# design.net
KiCad netlist of a schematic drawn in Altium Designer
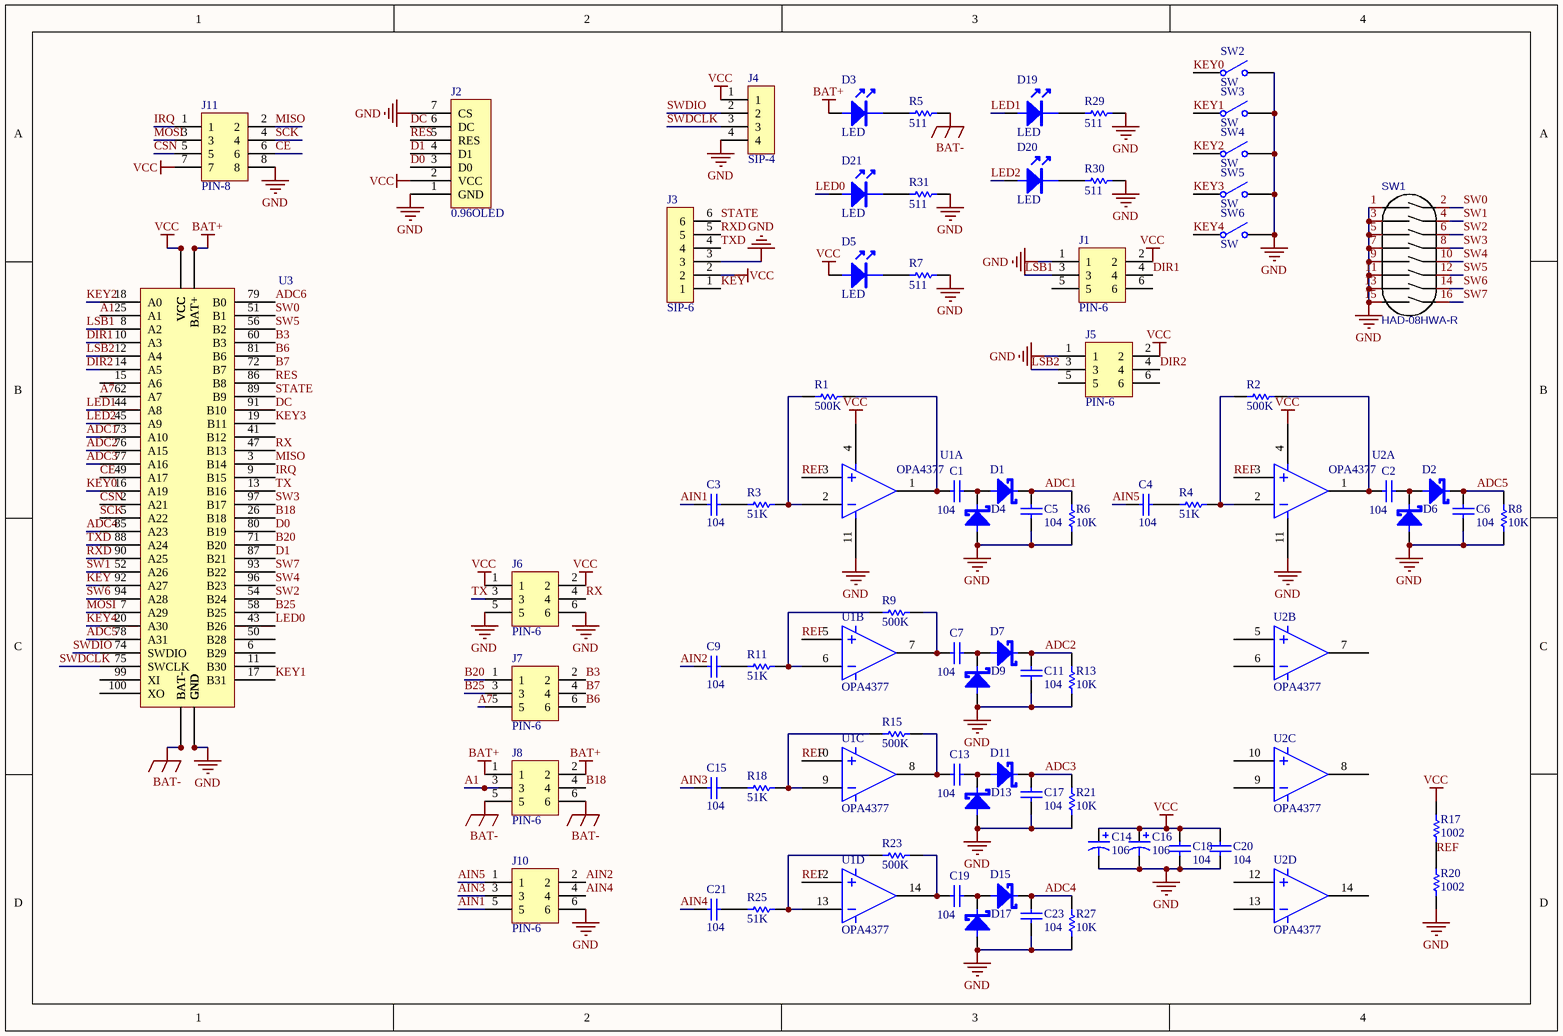
[diagram p0: 原理图.SchDoc]

(export (version "E")
  (design (tool "Eeschema 10.0.6"))
  (components
    (comp (ref "C1")
      (value "104")
      (footprint "C0603")
      (description "Capacitor")
      (fields (field (name "PUBLISHER") "Altium Limited"))
      (libsource (lib "容阻感") (part "电容"))
    )
    (comp (ref "C2")
      (value "104")
      (footprint "C0603")
      (description "Capacitor")
      (fields (field (name "PUBLISHER") "Altium Limited"))
      (libsource (lib "容阻感") (part "电容"))
    )
    (comp (ref "C3")
      (value "104")
      (footprint "C0603")
      (description "Capacitor")
      (fields (field (name "PUBLISHER") "Altium Limited"))
      (libsource (lib "容阻感") (part "电容"))
    )
    (comp (ref "C4")
      (value "104")
      (footprint "C0603")
      (description "Capacitor")
      (fields (field (name "PUBLISHER") "Altium Limited"))
      (libsource (lib "容阻感") (part "电容"))
    )
    (comp (ref "C5")
      (value "104")
      (footprint "C0603")
      (description "Capacitor")
      (fields (field (name "PUBLISHER") "Altium Limited"))
      (libsource (lib "容阻感") (part "电容"))
    )
    (comp (ref "C6")
      (value "104")
      (footprint "C0603")
      (description "Capacitor")
      (fields (field (name "PUBLISHER") "Altium Limited"))
      (libsource (lib "容阻感") (part "电容"))
    )
    (comp (ref "C7")
      (value "104")
      (footprint "C0603")
      (description "Capacitor")
      (fields (field (name "PUBLISHER") "Altium Limited"))
      (libsource (lib "容阻感") (part "电容"))
    )
    (comp (ref "C9")
      (value "104")
      (footprint "C0603")
      (description "Capacitor")
      (fields (field (name "PUBLISHER") "Altium Limited"))
      (libsource (lib "容阻感") (part "电容"))
    )
    (comp (ref "C11")
      (value "104")
      (footprint "C0603")
      (description "Capacitor")
      (fields (field (name "PUBLISHER") "Altium Limited"))
      (libsource (lib "容阻感") (part "电容"))
    )
    (comp (ref "C13")
      (value "104")
      (footprint "C0603")
      (description "Capacitor")
      (fields (field (name "PUBLISHER") "Altium Limited"))
      (libsource (lib "容阻感") (part "电容"))
    )
    (comp (ref "C14")
      (value "106")
      (footprint "3216-ce")
      (description "Polarized Capacitor (Axial)")
      (fields (field (name "PUBLISHER") "Altium Limited"))
      (libsource (lib "容阻感") (part "电解电容"))
    )
    (comp (ref "C15")
      (value "104")
      (footprint "C0603")
      (description "Capacitor")
      (fields (field (name "PUBLISHER") "Altium Limited"))
      (libsource (lib "容阻感") (part "电容"))
    )
    (comp (ref "C16")
      (value "106")
      (footprint "3216-ce")
      (description "Polarized Capacitor (Axial)")
      (fields (field (name "PUBLISHER") "Altium Limited"))
      (libsource (lib "容阻感") (part "电解电容"))
    )
    (comp (ref "C17")
      (value "104")
      (footprint "C0603")
      (description "Capacitor")
      (fields (field (name "PUBLISHER") "Altium Limited"))
      (libsource (lib "容阻感") (part "电容"))
    )
    (comp (ref "C18")
      (value "104")
      (footprint "C0603")
      (description "Capacitor")
      (fields (field (name "PUBLISHER") "Altium Limited"))
      (libsource (lib "容阻感") (part "电容"))
    )
    (comp (ref "C19")
      (value "104")
      (footprint "C0603")
      (description "Capacitor")
      (fields (field (name "PUBLISHER") "Altium Limited"))
      (libsource (lib "容阻感") (part "电容"))
    )
    (comp (ref "C20")
      (value "104")
      (footprint "C0603")
      (description "Capacitor")
      (fields (field (name "PUBLISHER") "Altium Limited"))
      (libsource (lib "容阻感") (part "电容"))
    )
    (comp (ref "C21")
      (value "104")
      (footprint "C0603")
      (description "Capacitor")
      (fields (field (name "PUBLISHER") "Altium Limited"))
      (libsource (lib "容阻感") (part "电容"))
    )
    (comp (ref "C23")
      (value "104")
      (footprint "C0603")
      (description "Capacitor")
      (fields (field (name "PUBLISHER") "Altium Limited"))
      (libsource (lib "容阻感") (part "电容"))
    )
    (comp (ref "D1")
      (value "肖特基")
      (footprint "SOD-523")
      (description "Schottky Diode")
      (libsource (lib "管子、") (part "肖特基"))
    )
    (comp (ref "D2")
      (value "肖特基")
      (footprint "SOD-523")
      (description "Schottky Diode")
      (libsource (lib "管子、") (part "肖特基"))
    )
    (comp (ref "D3") (value "LED") (footprint "LED 0603G") (libsource (lib "管子、") (part "LED")))
    (comp (ref "D4")
      (value "肖特基")
      (footprint "SOD-523")
      (description "Schottky Diode")
      (libsource (lib "管子、") (part "肖特基"))
    )
    (comp (ref "D5") (value "LED") (footprint "LED 0603G") (libsource (lib "管子、") (part "LED")))
    (comp (ref "D6")
      (value "肖特基")
      (footprint "SOD-523")
      (description "Schottky Diode")
      (libsource (lib "管子、") (part "肖特基"))
    )
    (comp (ref "D7")
      (value "肖特基")
      (footprint "SOD-523")
      (description "Schottky Diode")
      (libsource (lib "管子、") (part "肖特基"))
    )
    (comp (ref "D9")
      (value "肖特基")
      (footprint "SOD-523")
      (description "Schottky Diode")
      (libsource (lib "管子、") (part "肖特基"))
    )
    (comp (ref "D11")
      (value "肖特基")
      (footprint "SOD-523")
      (description "Schottky Diode")
      (libsource (lib "管子、") (part "肖特基"))
    )
    (comp (ref "D13")
      (value "肖特基")
      (footprint "SOD-523")
      (description "Schottky Diode")
      (libsource (lib "管子、") (part "肖特基"))
    )
    (comp (ref "D15")
      (value "肖特基")
      (footprint "SOD-523")
      (description "Schottky Diode")
      (libsource (lib "管子、") (part "肖特基"))
    )
    (comp (ref "D17")
      (value "肖特基")
      (footprint "SOD-523")
      (description "Schottky Diode")
      (libsource (lib "管子、") (part "肖特基"))
    )
    (comp (ref "D19") (value "LED") (footprint "LED 0603G") (libsource (lib "管子、") (part "LED")))
    (comp (ref "D20") (value "LED") (footprint "LED 0603G") (libsource (lib "管子、") (part "LED")))
    (comp (ref "D21") (value "LED") (footprint "LED 0603G") (libsource (lib "管子、") (part "LED")))
    (comp (ref "J1") (value "PIN-6") (footprint "2.54简易牛角座6P") (libsource (lib "接插件") (part "PIN-6")))
    (comp (ref "J2") (value "0.96OLED") (footprint "OLED 0.96") (libsource (lib "接插件") (part "OLED_SPI")))
    (comp (ref "J3") (value "SIP-6") (footprint "2.54排针1X6") (libsource (lib "接插件") (part "SIP-6")))
    (comp (ref "J4") (value "SIP-4") (footprint "XH2.54-4AB") (libsource (lib "接插件") (part "SIP-4")))
    (comp (ref "J5") (value "PIN-6") (footprint "2.54简易牛角座6P") (libsource (lib "接插件") (part "PIN-6")))
    (comp (ref "J6") (value "PIN-6") (footprint "P6smd") (libsource (lib "接插件") (part "PIN-6")))
    (comp (ref "J7") (value "PIN-6") (footprint "P6smd") (libsource (lib "接插件") (part "PIN-6")))
    (comp (ref "J8") (value "PIN-6") (footprint "P6smd") (libsource (lib "接插件") (part "PIN-6")))
    (comp (ref "J10") (value "PIN-6") (footprint "P6smd") (libsource (lib "接插件") (part "PIN-6")))
    (comp (ref "J11") (value "PIN-8") (footprint "2.54排针2X4") (libsource (lib "接插件") (part "PIN-8")))
    (comp (ref "R1")
      (value "500K")
      (footprint "R0603")
      (description "Resistor")
      (fields (field (name "PUBLISHER") "Altium Limited"))
      (libsource (lib "容阻感") (part "电阻"))
    )
    (comp (ref "R2")
      (value "500K")
      (footprint "R0603")
      (description "Resistor")
      (fields (field (name "PUBLISHER") "Altium Limited"))
      (libsource (lib "容阻感") (part "电阻"))
    )
    (comp (ref "R3")
      (value "51K")
      (footprint "R0603")
      (description "Resistor")
      (fields (field (name "PUBLISHER") "Altium Limited"))
      (libsource (lib "容阻感") (part "电阻"))
    )
    (comp (ref "R4")
      (value "51K")
      (footprint "R0603")
      (description "Resistor")
      (fields (field (name "PUBLISHER") "Altium Limited"))
      (libsource (lib "容阻感") (part "电阻"))
    )
    (comp (ref "R5")
      (value "511")
      (footprint "R0603")
      (description "Resistor")
      (fields (field (name "PUBLISHER") "Altium Limited"))
      (libsource (lib "容阻感") (part "电阻"))
    )
    (comp (ref "R6")
      (value "10K")
      (footprint "R0603")
      (description "Resistor")
      (fields (field (name "PUBLISHER") "Altium Limited"))
      (libsource (lib "容阻感") (part "电阻"))
    )
    (comp (ref "R7")
      (value "511")
      (footprint "R0603")
      (description "Resistor")
      (fields (field (name "PUBLISHER") "Altium Limited"))
      (libsource (lib "容阻感") (part "电阻"))
    )
    (comp (ref "R8")
      (value "10K")
      (footprint "R0603")
      (description "Resistor")
      (fields (field (name "PUBLISHER") "Altium Limited"))
      (libsource (lib "容阻感") (part "电阻"))
    )
    (comp (ref "R9")
      (value "500K")
      (footprint "R0603")
      (description "Resistor")
      (fields (field (name "PUBLISHER") "Altium Limited"))
      (libsource (lib "容阻感") (part "电阻"))
    )
    (comp (ref "R11")
      (value "51K")
      (footprint "R0603")
      (description "Resistor")
      (fields (field (name "PUBLISHER") "Altium Limited"))
      (libsource (lib "容阻感") (part "电阻"))
    )
    (comp (ref "R13")
      (value "10K")
      (footprint "R0603")
      (description "Resistor")
      (fields (field (name "PUBLISHER") "Altium Limited"))
      (libsource (lib "容阻感") (part "电阻"))
    )
    (comp (ref "R15")
      (value "500K")
      (footprint "R0603")
      (description "Resistor")
      (fields (field (name "PUBLISHER") "Altium Limited"))
      (libsource (lib "容阻感") (part "电阻"))
    )
    (comp (ref "R17")
      (value "1002")
      (footprint "R0603")
      (description "Resistor")
      (fields (field (name "PUBLISHER") "Altium Limited"))
      (libsource (lib "容阻感") (part "电阻"))
    )
    (comp (ref "R18")
      (value "51K")
      (footprint "R0603")
      (description "Resistor")
      (fields (field (name "PUBLISHER") "Altium Limited"))
      (libsource (lib "容阻感") (part "电阻"))
    )
    (comp (ref "R20")
      (value "1002")
      (footprint "R0603")
      (description "Resistor")
      (fields (field (name "PUBLISHER") "Altium Limited"))
      (libsource (lib "容阻感") (part "电阻"))
    )
    (comp (ref "R21")
      (value "10K")
      (footprint "R0603")
      (description "Resistor")
      (fields (field (name "PUBLISHER") "Altium Limited"))
      (libsource (lib "容阻感") (part "电阻"))
    )
    (comp (ref "R23")
      (value "500K")
      (footprint "R0603")
      (description "Resistor")
      (fields (field (name "PUBLISHER") "Altium Limited"))
      (libsource (lib "容阻感") (part "电阻"))
    )
    (comp (ref "R25")
      (value "51K")
      (footprint "R0603")
      (description "Resistor")
      (fields (field (name "PUBLISHER") "Altium Limited"))
      (libsource (lib "容阻感") (part "电阻"))
    )
    (comp (ref "R27")
      (value "10K")
      (footprint "R0603")
      (description "Resistor")
      (fields (field (name "PUBLISHER") "Altium Limited"))
      (libsource (lib "容阻感") (part "电阻"))
    )
    (comp (ref "R29")
      (value "511")
      (footprint "R0603")
      (description "Resistor")
      (fields (field (name "PUBLISHER") "Altium Limited"))
      (libsource (lib "容阻感") (part "电阻"))
    )
    (comp (ref "R30")
      (value "511")
      (footprint "R0603")
      (description "Resistor")
      (fields (field (name "PUBLISHER") "Altium Limited"))
      (libsource (lib "容阻感") (part "电阻"))
    )
    (comp (ref "R31")
      (value "511")
      (footprint "R0603")
      (description "Resistor")
      (fields (field (name "PUBLISHER") "Altium Limited"))
      (libsource (lib "容阻感") (part "电阻"))
    )
    (comp (ref "SW1")
      (value "HAD-08HWA-R")
      (footprint "拨码MCEMR-08-T")
      (fields (field (name "BOM_SUPPLIER PART") "C4682"))
      (libsource (lib "接插件") (part "8位拨码"))
    )
    (comp (ref "SW2")
      (value "SW")
      (footprint "SWT6*3")
      (description "Single-Pole, Single-Throw Switch")
      (libsource (lib "接插件") (part "Switch"))
    )
    (comp (ref "SW3")
      (value "SW")
      (footprint "SWT6*3")
      (description "Single-Pole, Single-Throw Switch")
      (libsource (lib "接插件") (part "Switch"))
    )
    (comp (ref "SW4")
      (value "SW")
      (footprint "SWT6*3")
      (description "Single-Pole, Single-Throw Switch")
      (libsource (lib "接插件") (part "Switch"))
    )
    (comp (ref "SW5")
      (value "SW")
      (footprint "SWT6*3")
      (description "Single-Pole, Single-Throw Switch")
      (libsource (lib "接插件") (part "Switch"))
    )
    (comp (ref "SW6")
      (value "SW")
      (footprint "SWT6*3")
      (description "Single-Pole, Single-Throw Switch")
      (libsource (lib "接插件") (part "Switch"))
    )
    (comp (ref "U1") (value "OPA4377") (footprint "TSSOP-14") (libsource (lib "IC") (part "4运放")))
    (comp (ref "U2") (value "OPA4377") (footprint "TSSOP-14") (libsource (lib "IC") (part "4运放")))
    (comp (ref "U3") (value "主控&驱动") (footprint "核心") (libsource (lib "接插件") (part "核心")))
  )
  (nets
    (net (code "1") (name "/A1") (class "Default")
      (node (ref "J8") (pin "3") (pinfunction "3_3") (pintype "passive"))
      (node (ref "U3") (pin "25") (pinfunction "A1_25") (pintype "passive"))
    )
    (net (code "2") (name "/A7") (class "Default")
      (node (ref "J7") (pin "5") (pinfunction "5_5") (pintype "passive"))
      (node (ref "U3") (pin "62") (pinfunction "A7_62") (pintype "passive"))
    )
    (net (code "3") (name "/ADC1") (class "Default")
      (node (ref "C5") (pin "2") (pinfunction "2_2") (pintype "passive"))
      (node (ref "D1") (pin "2") (pinfunction "K_2") (pintype "passive"))
      (node (ref "R6") (pin "1") (pinfunction "1_1") (pintype "passive"))
      (node (ref "U3") (pin "73") (pinfunction "A10_73") (pintype "passive"))
    )
    (net (code "4") (name "/ADC2") (class "Default")
      (node (ref "C11") (pin "2") (pinfunction "2_2") (pintype "passive"))
      (node (ref "D7") (pin "2") (pinfunction "K_2") (pintype "passive"))
      (node (ref "R13") (pin "1") (pinfunction "1_1") (pintype "passive"))
      (node (ref "U3") (pin "76") (pinfunction "A15_76") (pintype "passive"))
    )
    (net (code "5") (name "/ADC3") (class "Default")
      (node (ref "C17") (pin "2") (pinfunction "2_2") (pintype "passive"))
      (node (ref "D11") (pin "2") (pinfunction "K_2") (pintype "passive"))
      (node (ref "R21") (pin "1") (pinfunction "1_1") (pintype "passive"))
      (node (ref "U3") (pin "77") (pinfunction "A16_77") (pintype "passive"))
    )
    (net (code "6") (name "/ADC4") (class "Default")
      (node (ref "C23") (pin "2") (pinfunction "2_2") (pintype "passive"))
      (node (ref "D15") (pin "2") (pinfunction "K_2") (pintype "passive"))
      (node (ref "R27") (pin "1") (pinfunction "1_1") (pintype "passive"))
      (node (ref "U3") (pin "85") (pinfunction "A23_85") (pintype "passive"))
    )
    (net (code "7") (name "/ADC5") (class "Default")
      (node (ref "C6") (pin "2") (pinfunction "2_2") (pintype "passive"))
      (node (ref "D2") (pin "2") (pinfunction "K_2") (pintype "passive"))
      (node (ref "R8") (pin "1") (pinfunction "1_1") (pintype "passive"))
      (node (ref "U3") (pin "78") (pinfunction "A31_78") (pintype "passive"))
    )
    (net (code "8") (name "/ADC6") (class "Default")
      (node (ref "U3") (pin "79") (pinfunction "B0_79") (pintype "passive"))
    )
    (net (code "9") (name "/AIN1") (class "Default")
      (node (ref "C3") (pin "1") (pinfunction "1_1") (pintype "passive"))
      (node (ref "J10") (pin "5") (pinfunction "5_5") (pintype "passive"))
    )
    (net (code "10") (name "/AIN2") (class "Default")
      (node (ref "C9") (pin "1") (pinfunction "1_1") (pintype "passive"))
      (node (ref "J10") (pin "2") (pinfunction "2_2") (pintype "passive"))
    )
    (net (code "11") (name "/AIN3") (class "Default")
      (node (ref "C15") (pin "1") (pinfunction "1_1") (pintype "passive"))
      (node (ref "J10") (pin "3") (pinfunction "3_3") (pintype "passive"))
    )
    (net (code "12") (name "/AIN4") (class "Default")
      (node (ref "C21") (pin "1") (pinfunction "1_1") (pintype "passive"))
      (node (ref "J10") (pin "4") (pinfunction "4_4") (pintype "passive"))
    )
    (net (code "13") (name "/AIN5") (class "Default")
      (node (ref "C4") (pin "1") (pinfunction "1_1") (pintype "passive"))
      (node (ref "J10") (pin "1") (pinfunction "1_1") (pintype "passive"))
    )
    (net (code "14") (name "/B3") (class "Default")
      (node (ref "J7") (pin "2") (pinfunction "2_2") (pintype "passive"))
      (node (ref "U3") (pin "60") (pinfunction "B3_60") (pintype "passive"))
    )
    (net (code "15") (name "/B6") (class "Default")
      (node (ref "J7") (pin "6") (pinfunction "6_6") (pintype "passive"))
      (node (ref "U3") (pin "81") (pinfunction "B6_81") (pintype "passive"))
    )
    (net (code "16") (name "/B7") (class "Default")
      (node (ref "J7") (pin "4") (pinfunction "4_4") (pintype "passive"))
      (node (ref "U3") (pin "72") (pinfunction "B7_72") (pintype "passive"))
    )
    (net (code "17") (name "/B18") (class "Default")
      (node (ref "J8") (pin "4") (pinfunction "4_4") (pintype "passive"))
      (node (ref "U3") (pin "26") (pinfunction "B18_26") (pintype "passive"))
    )
    (net (code "18") (name "/B20") (class "Default")
      (node (ref "J7") (pin "1") (pinfunction "1_1") (pintype "passive"))
      (node (ref "U3") (pin "71") (pinfunction "B20_71") (pintype "passive"))
    )
    (net (code "19") (name "/B25") (class "Default")
      (node (ref "J7") (pin "3") (pinfunction "3_3") (pintype "passive"))
      (node (ref "U3") (pin "58") (pinfunction "B25_58") (pintype "passive"))
    )
    (net (code "20") (name "/CE") (class "Default")
      (node (ref "J11") (pin "6") (pinfunction "6_6") (pintype "passive"))
      (node (ref "U3") (pin "49") (pinfunction "A17_49") (pintype "passive"))
    )
    (net (code "21") (name "/CSN") (class "Default")
      (node (ref "J11") (pin "5") (pinfunction "5_5") (pintype "passive"))
      (node (ref "U3") (pin "2") (pinfunction "A21_2") (pintype "passive"))
    )
    (net (code "22") (name "/D0") (class "Default")
      (node (ref "J2") (pin "3") (pinfunction "D0_3") (pintype "passive"))
      (node (ref "U3") (pin "80") (pinfunction "B19_80") (pintype "passive"))
    )
    (net (code "23") (name "/D1") (class "Default")
      (node (ref "J2") (pin "4") (pinfunction "D1_4") (pintype "passive"))
      (node (ref "U3") (pin "87") (pinfunction "B21_87") (pintype "passive"))
    )
    (net (code "24") (name "/DC") (class "Default")
      (node (ref "J2") (pin "6") (pinfunction "DC_6") (pintype "passive"))
      (node (ref "U3") (pin "91") (pinfunction "B10_91") (pintype "passive"))
    )
    (net (code "25") (name "/DIR1") (class "Default")
      (node (ref "J1") (pin "4") (pinfunction "4_4") (pintype "passive"))
      (node (ref "U3") (pin "10") (pinfunction "A3_10") (pintype "passive"))
    )
    (net (code "26") (name "/DIR2") (class "Default")
      (node (ref "J5") (pin "4") (pinfunction "4_4") (pintype "passive"))
      (node (ref "U3") (pin "14") (pinfunction "A5_14") (pintype "passive"))
    )
    (net (code "27") (name "/IRQ") (class "Default")
      (node (ref "J11") (pin "1") (pinfunction "1_1") (pintype "passive"))
      (node (ref "U3") (pin "9") (pinfunction "B15_9") (pintype "passive"))
    )
    (net (code "28") (name "/KEY") (class "Default")
      (node (ref "J3") (pin "1") (pinfunction "1_1") (pintype "passive"))
      (node (ref "U3") (pin "92") (pinfunction "A27_92") (pintype "passive"))
    )
    (net (code "29") (name "/KEY0") (class "Default")
      (node (ref "SW2") (pin "1") (pinfunction "COMMON_1") (pintype "passive"))
      (node (ref "U3") (pin "16") (pinfunction "A19_16") (pintype "passive"))
    )
    (net (code "30") (name "/KEY1") (class "Default")
      (node (ref "SW3") (pin "1") (pinfunction "COMMON_1") (pintype "passive"))
      (node (ref "U3") (pin "17") (pinfunction "B31_17") (pintype "passive"))
    )
    (net (code "31") (name "/KEY2") (class "Default")
      (node (ref "SW4") (pin "1") (pinfunction "COMMON_1") (pintype "passive"))
      (node (ref "U3") (pin "18") (pinfunction "A0_18") (pintype "passive"))
    )
    (net (code "32") (name "/KEY3") (class "Default")
      (node (ref "SW5") (pin "1") (pinfunction "COMMON_1") (pintype "passive"))
      (node (ref "U3") (pin "19") (pinfunction "B11_19") (pintype "passive"))
    )
    (net (code "33") (name "/KEY4") (class "Default")
      (node (ref "SW6") (pin "1") (pinfunction "COMMON_1") (pintype "passive"))
      (node (ref "U3") (pin "20") (pinfunction "A30_20") (pintype "passive"))
    )
    (net (code "34") (name "/LED0") (class "Default")
      (node (ref "D21") (pin "A") (pinfunction "1_A") (pintype "passive"))
      (node (ref "U3") (pin "43") (pinfunction "B26_43") (pintype "passive"))
    )
    (net (code "35") (name "/LED1") (class "Default")
      (node (ref "D19") (pin "A") (pinfunction "1_A") (pintype "passive"))
      (node (ref "U3") (pin "44") (pinfunction "A8_44") (pintype "passive"))
    )
    (net (code "36") (name "/LED2") (class "Default")
      (node (ref "D20") (pin "A") (pinfunction "1_A") (pintype "passive"))
      (node (ref "U3") (pin "45") (pinfunction "A9_45") (pintype "passive"))
    )
    (net (code "37") (name "/LSB1") (class "Default")
      (node (ref "J1") (pin "3") (pinfunction "3_3") (pintype "passive"))
      (node (ref "U3") (pin "8") (pinfunction "A2_8") (pintype "passive"))
    )
    (net (code "38") (name "/LSB2") (class "Default")
      (node (ref "J5") (pin "3") (pinfunction "3_3") (pintype "passive"))
      (node (ref "U3") (pin "12") (pinfunction "A4_12") (pintype "passive"))
    )
    (net (code "39") (name "/MISO") (class "Default")
      (node (ref "J11") (pin "2") (pinfunction "2_2") (pintype "passive"))
      (node (ref "U3") (pin "3") (pinfunction "B14_3") (pintype "passive"))
    )
    (net (code "40") (name "/MOSI") (class "Default")
      (node (ref "J11") (pin "3") (pinfunction "3_3") (pintype "passive"))
      (node (ref "U3") (pin "7") (pinfunction "A29_7") (pintype "passive"))
    )
    (net (code "41") (name "/REF") (class "Default")
      (node (ref "R17") (pin "1") (pinfunction "1_1") (pintype "passive"))
      (node (ref "R20") (pin "2") (pinfunction "2_2") (pintype "passive"))
      (node (ref "U1") (pin "10") (pintype "passive"))
      (node (ref "U1") (pin "12") (pintype "passive"))
      (node (ref "U1") (pin "3") (pintype "passive"))
      (node (ref "U1") (pin "5") (pintype "passive"))
      (node (ref "U2") (pin "3") (pintype "passive"))
    )
    (net (code "42") (name "/RES") (class "Default")
      (node (ref "J2") (pin "5") (pinfunction "RES_5") (pintype "passive"))
      (node (ref "U3") (pin "86") (pinfunction "B8_86") (pintype "passive"))
    )
    (net (code "43") (name "/RX") (class "Default")
      (node (ref "J6") (pin "4") (pinfunction "4_4") (pintype "passive"))
      (node (ref "U3") (pin "47") (pinfunction "B13_47") (pintype "passive"))
    )
    (net (code "44") (name "/RXD") (class "Default")
      (node (ref "J3") (pin "5") (pinfunction "5_5") (pintype "passive"))
      (node (ref "U3") (pin "90") (pinfunction "A25_90") (pintype "passive"))
    )
    (net (code "45") (name "/SCK") (class "Default")
      (node (ref "J11") (pin "4") (pinfunction "4_4") (pintype "passive"))
      (node (ref "U3") (pin "5") (pinfunction "A22_5") (pintype "passive"))
    )
    (net (code "46") (name "/STATE") (class "Default")
      (node (ref "J3") (pin "6") (pinfunction "6_6") (pintype "passive"))
      (node (ref "U3") (pin "89") (pinfunction "B9_89") (pintype "passive"))
    )
    (net (code "47") (name "/SW0") (class "Default")
      (node (ref "SW1") (pin "2") (pinfunction "16_2") (pintype "passive"))
      (node (ref "U3") (pin "51") (pinfunction "B1_51") (pintype "passive"))
    )
    (net (code "48") (name "/SW1") (class "Default")
      (node (ref "SW1") (pin "4") (pinfunction "15_4") (pintype "passive"))
      (node (ref "U3") (pin "52") (pinfunction "A26_52") (pintype "passive"))
    )
    (net (code "49") (name "/SW2") (class "Default")
      (node (ref "SW1") (pin "6") (pinfunction "14_6") (pintype "passive"))
      (node (ref "U3") (pin "54") (pinfunction "B24_54") (pintype "passive"))
    )
    (net (code "50") (name "/SW3") (class "Default")
      (node (ref "SW1") (pin "8") (pinfunction "13_8") (pintype "passive"))
      (node (ref "U3") (pin "97") (pinfunction "B17_97") (pintype "passive"))
    )
    (net (code "51") (name "/SW4") (class "Default")
      (node (ref "SW1") (pin "10") (pinfunction "12_10") (pintype "passive"))
      (node (ref "U3") (pin "96") (pinfunction "B23_96") (pintype "passive"))
    )
    (net (code "52") (name "/SW5") (class "Default")
      (node (ref "SW1") (pin "12") (pinfunction "11_12") (pintype "passive"))
      (node (ref "U3") (pin "56") (pinfunction "B2_56") (pintype "passive"))
    )
    (net (code "53") (name "/SW6") (class "Default")
      (node (ref "SW1") (pin "14") (pinfunction "10_14") (pintype "passive"))
      (node (ref "U3") (pin "94") (pinfunction "A28_94") (pintype "passive"))
    )
    (net (code "54") (name "/SW7") (class "Default")
      (node (ref "SW1") (pin "16") (pinfunction "9_16") (pintype "passive"))
      (node (ref "U3") (pin "93") (pinfunction "B22_93") (pintype "passive"))
    )
    (net (code "55") (name "/SWDCLK") (class "Default")
      (node (ref "J4") (pin "3") (pinfunction "3_3") (pintype "passive"))
      (node (ref "U3") (pin "75") (pinfunction "SWCLK_75") (pintype "passive"))
    )
    (net (code "56") (name "/SWDIO") (class "Default")
      (node (ref "J4") (pin "2") (pinfunction "2_2") (pintype "passive"))
      (node (ref "U3") (pin "74") (pinfunction "SWDIO_74") (pintype "passive"))
    )
    (net (code "57") (name "/TX") (class "Default")
      (node (ref "J6") (pin "3") (pinfunction "3_3") (pintype "passive"))
      (node (ref "U3") (pin "13") (pinfunction "B16_13") (pintype "passive"))
    )
    (net (code "58") (name "/TXD") (class "Default")
      (node (ref "J3") (pin "4") (pinfunction "4_4") (pintype "passive"))
      (node (ref "U3") (pin "88") (pinfunction "A24_88") (pintype "passive"))
    )
    (net (code "59") (name "BAT+") (class "Default")
      (node (ref "D3") (pin "A") (pinfunction "1_A") (pintype "passive"))
      (node (ref "J8") (pin "1") (pinfunction "1_1") (pintype "passive"))
      (node (ref "J8") (pin "2") (pinfunction "2_2") (pintype "passive"))
      (node (ref "U3") (pin "33") (pinfunction "BAT+_33") (pintype "passive"))
      (node (ref "U3") (pin "34") (pinfunction "BAT+_34") (pintype "passive"))
      (node (ref "U3") (pin "35") (pinfunction "BAT+_35") (pintype "passive"))
    )
    (net (code "60") (name "BAT-") (class "Default")
      (node (ref "J8") (pin "5") (pinfunction "5_5") (pintype "passive"))
      (node (ref "J8") (pin "6") (pinfunction "6_6") (pintype "passive"))
      (node (ref "R5") (pin "1") (pinfunction "1_1") (pintype "passive"))
      (node (ref "U3") (pin "37") (pinfunction "BAT-_37") (pintype "passive"))
      (node (ref "U3") (pin "38") (pinfunction "BAT-_38") (pintype "passive"))
      (node (ref "U3") (pin "39") (pinfunction "BAT-_39") (pintype "passive"))
      (node (ref "U3") (pin "40") (pinfunction "BAT-_40") (pintype "passive"))
    )
    (net (code "61") (name "GND") (class "Default")
      (node (ref "C11") (pin "1") (pinfunction "1_1") (pintype "passive"))
      (node (ref "C14") (pin "2") (pinfunction "2_2") (pintype "passive"))
      (node (ref "C16") (pin "2") (pinfunction "2_2") (pintype "passive"))
      (node (ref "C17") (pin "1") (pinfunction "1_1") (pintype "passive"))
      (node (ref "C18") (pin "1") (pinfunction "1_1") (pintype "passive"))
      (node (ref "C20") (pin "1") (pinfunction "1_1") (pintype "passive"))
      (node (ref "C23") (pin "1") (pinfunction "1_1") (pintype "passive"))
      (node (ref "C5") (pin "1") (pinfunction "1_1") (pintype "passive"))
      (node (ref "C6") (pin "1") (pinfunction "1_1") (pintype "passive"))
      (node (ref "D13") (pin "1") (pinfunction "A_1") (pintype "passive"))
      (node (ref "D17") (pin "1") (pinfunction "A_1") (pintype "passive"))
      (node (ref "D4") (pin "1") (pinfunction "A_1") (pintype "passive"))
      (node (ref "D6") (pin "1") (pinfunction "A_1") (pintype "passive"))
      (node (ref "D9") (pin "1") (pinfunction "A_1") (pintype "passive"))
      (node (ref "J1") (pin "1") (pinfunction "1_1") (pintype "passive"))
      (node (ref "J10") (pin "6") (pinfunction "6_6") (pintype "passive"))
      (node (ref "J11") (pin "8") (pinfunction "8_8") (pintype "passive"))
      (node (ref "J2") (pin "1") (pinfunction "GND_1") (pintype "passive"))
      (node (ref "J2") (pin "7") (pinfunction "CS_7") (pintype "passive"))
      (node (ref "J3") (pin "3") (pinfunction "3_3") (pintype "passive"))
      (node (ref "J4") (pin "4") (pinfunction "4_4") (pintype "passive"))
      (node (ref "J5") (pin "1") (pinfunction "1_1") (pintype "passive"))
      (node (ref "J6") (pin "5") (pinfunction "5_5") (pintype "passive"))
      (node (ref "J6") (pin "6") (pinfunction "6_6") (pintype "passive"))
      (node (ref "R13") (pin "2") (pinfunction "2_2") (pintype "passive"))
      (node (ref "R20") (pin "1") (pinfunction "1_1") (pintype "passive"))
      (node (ref "R21") (pin "2") (pinfunction "2_2") (pintype "passive"))
      (node (ref "R27") (pin "2") (pinfunction "2_2") (pintype "passive"))
      (node (ref "R29") (pin "1") (pinfunction "1_1") (pintype "passive"))
      (node (ref "R30") (pin "1") (pinfunction "1_1") (pintype "passive"))
      (node (ref "R31") (pin "1") (pinfunction "1_1") (pintype "passive"))
      (node (ref "R6") (pin "2") (pinfunction "2_2") (pintype "passive"))
      (node (ref "R7") (pin "1") (pinfunction "1_1") (pintype "passive"))
      (node (ref "R8") (pin "2") (pinfunction "2_2") (pintype "passive"))
      (node (ref "SW1") (pin "1") (pinfunction "1_1") (pintype "passive"))
      (node (ref "SW1") (pin "11") (pinfunction "6_11") (pintype "passive"))
      (node (ref "SW1") (pin "13") (pinfunction "7_13") (pintype "passive"))
      (node (ref "SW1") (pin "15") (pinfunction "8_15") (pintype "passive"))
      (node (ref "SW1") (pin "3") (pinfunction "2_3") (pintype "passive"))
      (node (ref "SW1") (pin "5") (pinfunction "3_5") (pintype "passive"))
      (node (ref "SW1") (pin "7") (pinfunction "4_7") (pintype "passive"))
      (node (ref "SW1") (pin "9") (pinfunction "5_9") (pintype "passive"))
      (node (ref "SW2") (pin "2") (pinfunction "NO_2") (pintype "passive"))
      (node (ref "SW3") (pin "2") (pinfunction "NO_2") (pintype "passive"))
      (node (ref "SW4") (pin "2") (pinfunction "NO_2") (pintype "passive"))
      (node (ref "SW5") (pin "2") (pinfunction "NO_2") (pintype "passive"))
      (node (ref "SW6") (pin "2") (pinfunction "NO_2") (pintype "passive"))
      (node (ref "U1") (pin "11") (pintype "passive"))
      (node (ref "U2") (pin "11") (pintype "passive"))
      (node (ref "U3") (pin "21") (pinfunction "GND_21") (pintype "passive"))
      (node (ref "U3") (pin "22") (pinfunction "GND_22") (pintype "passive"))
      (node (ref "U3") (pin "24") (pinfunction "GND_24") (pintype "passive"))
      (node (ref "U3") (pin "28") (pinfunction "GND_28") (pintype "passive"))
      (node (ref "U3") (pin "30") (pinfunction "GND_30") (pintype "passive"))
      (node (ref "U3") (pin "32") (pinfunction "GND_32") (pintype "passive"))
      (node (ref "U3") (pin "36") (pinfunction "GND_36") (pintype "passive"))
      (node (ref "U3") (pin "4") (pinfunction "GND_4") (pintype "passive"))
      (node (ref "U3") (pin "42") (pinfunction "GND_42") (pintype "passive"))
      (node (ref "U3") (pin "46") (pinfunction "GND_46") (pintype "passive"))
      (node (ref "U3") (pin "48") (pinfunction "GND_48") (pintype "passive"))
      (node (ref "U3") (pin "53") (pinfunction "GND_53") (pintype "passive"))
      (node (ref "U3") (pin "55") (pinfunction "GND_55") (pintype "passive"))
      (node (ref "U3") (pin "57") (pinfunction "GND_57") (pintype "passive"))
      (node (ref "U3") (pin "59") (pinfunction "GND_59") (pintype "passive"))
      (node (ref "U3") (pin "61") (pinfunction "GND_61") (pintype "passive"))
      (node (ref "U3") (pin "63") (pinfunction "GND_63") (pintype "passive"))
      (node (ref "U3") (pin "64") (pinfunction "GND_64") (pintype "passive"))
      (node (ref "U3") (pin "66") (pinfunction "GND_66") (pintype "passive"))
      (node (ref "U3") (pin "68") (pinfunction "GND_68") (pintype "passive"))
      (node (ref "U3") (pin "69") (pinfunction "GND_69") (pintype "passive"))
      (node (ref "U3") (pin "70") (pinfunction "GND_70") (pintype "passive"))
      (node (ref "U3") (pin "84") (pinfunction "GND_84") (pintype "passive"))
      (node (ref "U3") (pin "98") (pinfunction "GND_98") (pintype "passive"))
    )
    (net (code "62") (name "Net-(C1-Pad1)") (class "Default")
      (node (ref "C1") (pin "1") (pinfunction "1_1") (pintype "passive"))
      (node (ref "R1") (pin "1") (pinfunction "1_1") (pintype "passive"))
      (node (ref "U1") (pin "1") (pintype "passive"))
    )
    (net (code "63") (name "Net-(C2-Pad1)") (class "Default")
      (node (ref "C2") (pin "1") (pinfunction "1_1") (pintype "passive"))
      (node (ref "R2") (pin "1") (pinfunction "1_1") (pintype "passive"))
      (node (ref "U2") (pin "1") (pintype "passive"))
    )
    (net (code "64") (name "Net-(C3-Pad2)") (class "Default")
      (node (ref "C3") (pin "2") (pinfunction "2_2") (pintype "passive"))
      (node (ref "R3") (pin "2") (pinfunction "2_2") (pintype "passive"))
    )
    (net (code "65") (name "Net-(C4-Pad2)") (class "Default")
      (node (ref "C4") (pin "2") (pinfunction "2_2") (pintype "passive"))
      (node (ref "R4") (pin "2") (pinfunction "2_2") (pintype "passive"))
    )
    (net (code "66") (name "Net-(C7-Pad1)") (class "Default")
      (node (ref "C7") (pin "1") (pinfunction "1_1") (pintype "passive"))
      (node (ref "R9") (pin "1") (pinfunction "1_1") (pintype "passive"))
      (node (ref "U1") (pin "7") (pintype "passive"))
    )
    (net (code "67") (name "Net-(C9-Pad2)") (class "Default")
      (node (ref "C9") (pin "2") (pinfunction "2_2") (pintype "passive"))
      (node (ref "R11") (pin "2") (pinfunction "2_2") (pintype "passive"))
    )
    (net (code "68") (name "Net-(C13-Pad1)") (class "Default")
      (node (ref "C13") (pin "1") (pinfunction "1_1") (pintype "passive"))
      (node (ref "R15") (pin "1") (pinfunction "1_1") (pintype "passive"))
      (node (ref "U1") (pin "8") (pintype "passive"))
    )
    (net (code "69") (name "Net-(C15-Pad2)") (class "Default")
      (node (ref "C15") (pin "2") (pinfunction "2_2") (pintype "passive"))
      (node (ref "R18") (pin "2") (pinfunction "2_2") (pintype "passive"))
    )
    (net (code "70") (name "Net-(C19-Pad1)") (class "Default")
      (node (ref "C19") (pin "1") (pinfunction "1_1") (pintype "passive"))
      (node (ref "R23") (pin "1") (pinfunction "1_1") (pintype "passive"))
      (node (ref "U1") (pin "14") (pintype "passive"))
    )
    (net (code "71") (name "Net-(C21-Pad2)") (class "Default")
      (node (ref "C21") (pin "2") (pinfunction "2_2") (pintype "passive"))
      (node (ref "R25") (pin "2") (pinfunction "2_2") (pintype "passive"))
    )
    (net (code "72") (name "Net-(D1-A)") (class "Default")
      (node (ref "C1") (pin "2") (pinfunction "2_2") (pintype "passive"))
      (node (ref "D1") (pin "1") (pinfunction "A_1") (pintype "passive"))
      (node (ref "D4") (pin "2") (pinfunction "K_2") (pintype "passive"))
    )
    (net (code "73") (name "Net-(D2-A)") (class "Default")
      (node (ref "C2") (pin "2") (pinfunction "2_2") (pintype "passive"))
      (node (ref "D2") (pin "1") (pinfunction "A_1") (pintype "passive"))
      (node (ref "D6") (pin "2") (pinfunction "K_2") (pintype "passive"))
    )
    (net (code "74") (name "Net-(D3-2)") (class "Default")
      (node (ref "D3") (pin "K") (pinfunction "2_K") (pintype "passive"))
      (node (ref "R5") (pin "2") (pinfunction "2_2") (pintype "passive"))
    )
    (net (code "75") (name "Net-(D5-2)") (class "Default")
      (node (ref "D5") (pin "K") (pinfunction "2_K") (pintype "passive"))
      (node (ref "R7") (pin "2") (pinfunction "2_2") (pintype "passive"))
    )
    (net (code "76") (name "Net-(D7-A)") (class "Default")
      (node (ref "C7") (pin "2") (pinfunction "2_2") (pintype "passive"))
      (node (ref "D7") (pin "1") (pinfunction "A_1") (pintype "passive"))
      (node (ref "D9") (pin "2") (pinfunction "K_2") (pintype "passive"))
    )
    (net (code "77") (name "Net-(D11-A)") (class "Default")
      (node (ref "C13") (pin "2") (pinfunction "2_2") (pintype "passive"))
      (node (ref "D11") (pin "1") (pinfunction "A_1") (pintype "passive"))
      (node (ref "D13") (pin "2") (pinfunction "K_2") (pintype "passive"))
    )
    (net (code "78") (name "Net-(D15-A)") (class "Default")
      (node (ref "C19") (pin "2") (pinfunction "2_2") (pintype "passive"))
      (node (ref "D15") (pin "1") (pinfunction "A_1") (pintype "passive"))
      (node (ref "D17") (pin "2") (pinfunction "K_2") (pintype "passive"))
    )
    (net (code "79") (name "Net-(D19-2)") (class "Default")
      (node (ref "D19") (pin "K") (pinfunction "2_K") (pintype "passive"))
      (node (ref "R29") (pin "2") (pinfunction "2_2") (pintype "passive"))
    )
    (net (code "80") (name "Net-(D20-2)") (class "Default")
      (node (ref "D20") (pin "K") (pinfunction "2_K") (pintype "passive"))
      (node (ref "R30") (pin "2") (pinfunction "2_2") (pintype "passive"))
    )
    (net (code "81") (name "Net-(D21-2)") (class "Default")
      (node (ref "D21") (pin "K") (pinfunction "2_K") (pintype "passive"))
      (node (ref "R31") (pin "2") (pinfunction "2_2") (pintype "passive"))
    )
    (net (code "82") (name "Net-(R1-Pad2)") (class "Default")
      (node (ref "R1") (pin "2") (pinfunction "2_2") (pintype "passive"))
      (node (ref "R3") (pin "1") (pinfunction "1_1") (pintype "passive"))
      (node (ref "U1") (pin "2") (pintype "passive"))
    )
    (net (code "83") (name "Net-(R2-Pad2)") (class "Default")
      (node (ref "R2") (pin "2") (pinfunction "2_2") (pintype "passive"))
      (node (ref "R4") (pin "1") (pinfunction "1_1") (pintype "passive"))
      (node (ref "U2") (pin "2") (pintype "passive"))
    )
    (net (code "84") (name "Net-(R11-Pad1)") (class "Default")
      (node (ref "R11") (pin "1") (pinfunction "1_1") (pintype "passive"))
      (node (ref "R9") (pin "2") (pinfunction "2_2") (pintype "passive"))
      (node (ref "U1") (pin "6") (pintype "passive"))
    )
    (net (code "85") (name "Net-(R15-Pad2)") (class "Default")
      (node (ref "R15") (pin "2") (pinfunction "2_2") (pintype "passive"))
      (node (ref "R18") (pin "1") (pinfunction "1_1") (pintype "passive"))
      (node (ref "U1") (pin "9") (pintype "passive"))
    )
    (net (code "86") (name "Net-(R23-Pad2)") (class "Default")
      (node (ref "R23") (pin "2") (pinfunction "2_2") (pintype "passive"))
      (node (ref "R25") (pin "1") (pinfunction "1_1") (pintype "passive"))
      (node (ref "U1") (pin "13") (pintype "passive"))
    )
    (net (code "87") (name "VCC") (class "Default")
      (node (ref "C14") (pin "1") (pinfunction "1_1") (pintype "passive"))
      (node (ref "C16") (pin "1") (pinfunction "1_1") (pintype "passive"))
      (node (ref "C18") (pin "2") (pinfunction "2_2") (pintype "passive"))
      (node (ref "C20") (pin "2") (pinfunction "2_2") (pintype "passive"))
      (node (ref "D5") (pin "A") (pinfunction "1_A") (pintype "passive"))
      (node (ref "J1") (pin "2") (pinfunction "2_2") (pintype "passive"))
      (node (ref "J11") (pin "7") (pinfunction "7_7") (pintype "passive"))
      (node (ref "J2") (pin "2") (pinfunction "VCC_2") (pintype "passive"))
      (node (ref "J3") (pin "2") (pinfunction "2_2") (pintype "passive"))
      (node (ref "J4") (pin "1") (pinfunction "1_1") (pintype "passive"))
      (node (ref "J5") (pin "2") (pinfunction "2_2") (pintype "passive"))
      (node (ref "J6") (pin "1") (pinfunction "1_1") (pintype "passive"))
      (node (ref "J6") (pin "2") (pinfunction "2_2") (pintype "passive"))
      (node (ref "R17") (pin "2") (pinfunction "2_2") (pintype "passive"))
      (node (ref "U1") (pin "4") (pintype "passive"))
      (node (ref "U2") (pin "4") (pintype "passive"))
      (node (ref "U3") (pin "1") (pinfunction "VCC_1") (pintype "passive"))
      (node (ref "U3") (pin "23") (pinfunction "VCC_23") (pintype "passive"))
      (node (ref "U3") (pin "27") (pinfunction "VCC_27") (pintype "passive"))
      (node (ref "U3") (pin "29") (pinfunction "VCC_29") (pintype "passive"))
      (node (ref "U3") (pin "31") (pinfunction "VCC_31") (pintype "passive"))
      (node (ref "U3") (pin "65") (pinfunction "VCC_65") (pintype "passive"))
      (node (ref "U3") (pin "67") (pinfunction "VCC_67") (pintype "passive"))
      (node (ref "U3") (pin "82") (pinfunction "VCC_82") (pintype "passive"))
      (node (ref "U3") (pin "83") (pinfunction "VCC_83") (pintype "passive"))
      (node (ref "U3") (pin "95") (pinfunction "VCC_95") (pintype "passive"))
    )
    (net (code "88") (name "unconnected-(J1-Pad5)") (class "Default")
      (node (ref "J1") (pin "5") (pinfunction "5_5") (pintype "passive"))
    )
    (net (code "89") (name "unconnected-(J1-Pad6)") (class "Default")
      (node (ref "J1") (pin "6") (pinfunction "6_6") (pintype "passive"))
    )
    (net (code "90") (name "unconnected-(J5-Pad5)") (class "Default")
      (node (ref "J5") (pin "5") (pinfunction "5_5") (pintype "passive"))
    )
    (net (code "91") (name "unconnected-(J5-Pad6)") (class "Default")
      (node (ref "J5") (pin "6") (pinfunction "6_6") (pintype "passive"))
    )
    (net (code "92") (name "unconnected-(U2-Pad5)") (class "Default")
      (node (ref "U2") (pin "5") (pintype "passive"))
    )
    (net (code "93") (name "unconnected-(U2-Pad6)") (class "Default")
      (node (ref "U2") (pin "6") (pintype "passive"))
    )
    (net (code "94") (name "unconnected-(U2-Pad7)") (class "Default")
      (node (ref "U2") (pin "7") (pintype "passive"))
    )
    (net (code "95") (name "unconnected-(U2-Pad8)") (class "Default")
      (node (ref "U2") (pin "8") (pintype "passive"))
    )
    (net (code "96") (name "unconnected-(U2-Pad9)") (class "Default")
      (node (ref "U2") (pin "9") (pintype "passive"))
    )
    (net (code "97") (name "unconnected-(U2-Pad10)") (class "Default")
      (node (ref "U2") (pin "10") (pintype "passive"))
    )
    (net (code "98") (name "unconnected-(U2-Pad12)") (class "Default")
      (node (ref "U2") (pin "12") (pintype "passive"))
    )
    (net (code "99") (name "unconnected-(U2-Pad13)") (class "Default")
      (node (ref "U2") (pin "13") (pintype "passive"))
    )
    (net (code "100") (name "unconnected-(U2-Pad14)") (class "Default")
      (node (ref "U2") (pin "14") (pintype "passive"))
    )
    (net (code "101") (name "unconnected-(U3-A6-Pad15)") (class "Default")
      (node (ref "U3") (pin "15") (pinfunction "A6_15") (pintype "passive"))
    )
    (net (code "102") (name "unconnected-(U3-B12-Pad41)") (class "Default")
      (node (ref "U3") (pin "41") (pinfunction "B12_41") (pintype "passive"))
    )
    (net (code "103") (name "unconnected-(U3-B28-Pad50)") (class "Default")
      (node (ref "U3") (pin "50") (pinfunction "B28_50") (pintype "passive"))
    )
    (net (code "104") (name "unconnected-(U3-B29-Pad6)") (class "Default")
      (node (ref "U3") (pin "6") (pinfunction "B29_6") (pintype "passive"))
    )
    (net (code "105") (name "unconnected-(U3-B30-Pad11)") (class "Default")
      (node (ref "U3") (pin "11") (pinfunction "B30_11") (pintype "passive"))
    )
    (net (code "106") (name "unconnected-(U3-XI-Pad99)") (class "Default")
      (node (ref "U3") (pin "99") (pinfunction "XI_99") (pintype "passive"))
    )
    (net (code "107") (name "unconnected-(U3-XO-Pad100)") (class "Default")
      (node (ref "U3") (pin "100") (pinfunction "XO_100") (pintype "passive"))
    )
  )
)
